# motor_driver.net
KiCad netlist of a schematic drawn in Altium Designer
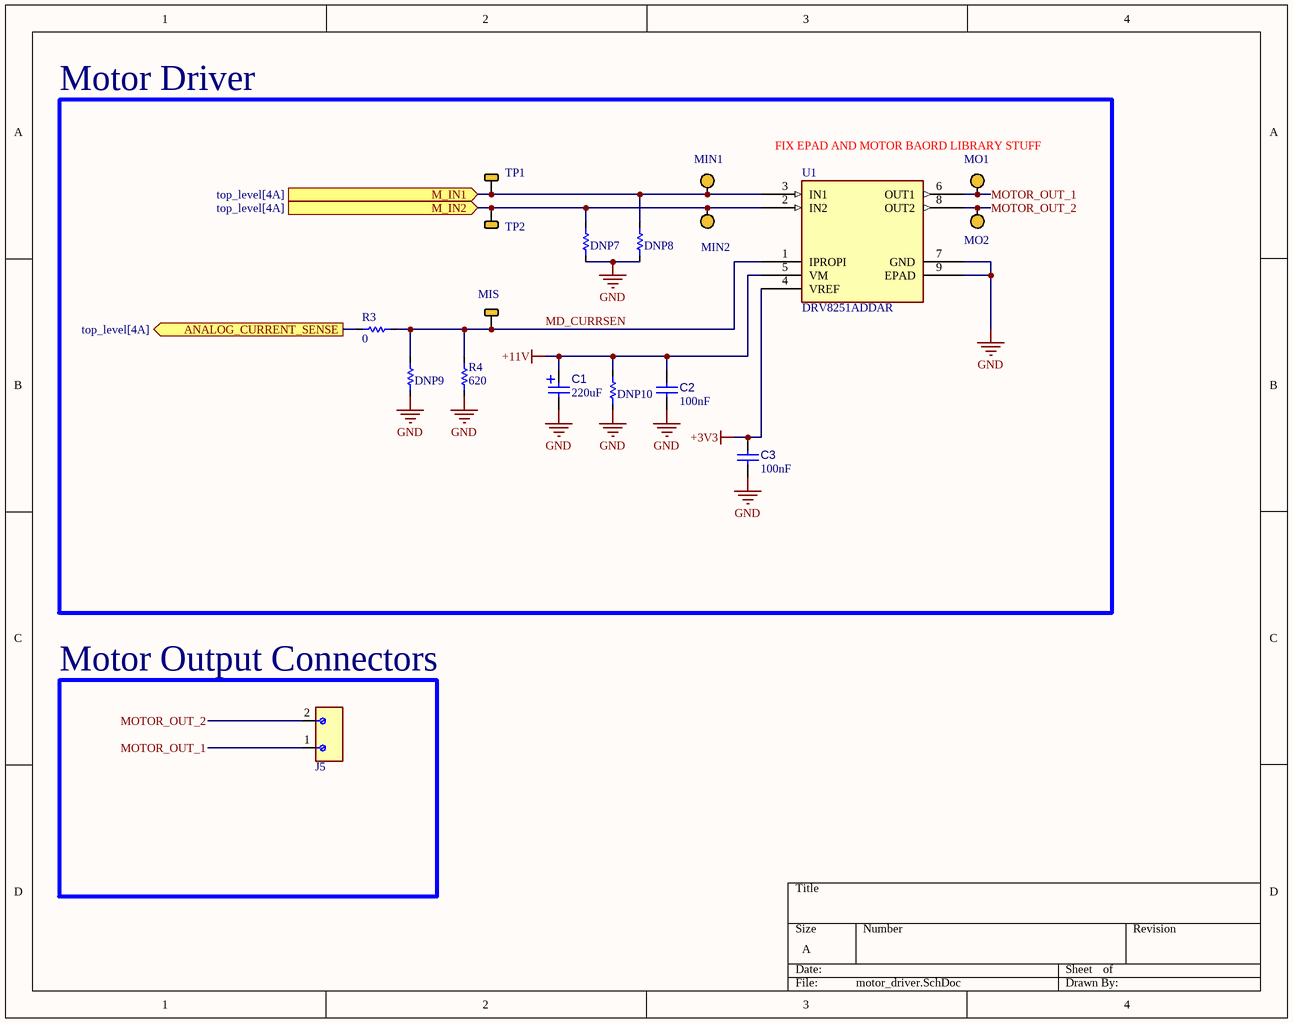
[diagram p0: motor_driver.SchDoc]

(export (version "E")
  (design (tool "Eeschema 10.0.6"))
  (components
    (comp (ref "C1")
      (value "220uF")
      (footprint "C - 860020574012")
      (description "860020574012 - 220 µF 35 V Aluminum Electrolytic Capacitors Radial, Can 2000 Hrs @ 105°C")
      (fields (field (name "Comment") "860020574012"))
      (libsource (lib "power_board_schhlib") (part "C - CAP ELC 220uF 35V 20% CAN"))
    )
    (comp (ref "C2")
      (value "100nF")
      (footprint "CAP_0603")
      (description "GRM188R72A104KA35D - 0.1 µF ±10% 100V Ceramic Capacitor X7R 0603 (1608 Metric)")
      (fields (field (name "Comment") "C - CAP CER 100nF 100V 10% 0603"))
      (libsource (lib "power_board_schhlib") (part "C - CAP CER 100nF 100V 10% 0603"))
    )
    (comp (ref "C3")
      (value "100nF")
      (footprint "CAP_0603")
      (description "GRM188R72A104KA35D - 0.1 µF ±10% 100V Ceramic Capacitor X7R 0603 (1608 Metric)")
      (fields (field (name "Comment") "C - CAP CER 100nF 100V 10% 0603"))
      (libsource (lib "power_board_schhlib") (part "C - CAP CER 100nF 100V 10% 0603"))
    )
    (comp (ref "DNP7")
      (value "DNP - DNP PAD 0603")
      (footprint "DNP 0603")
      (libsource (lib "motor_board_schhlib") (part "DNP - DNP PAD 0603"))
    )
    (comp (ref "DNP8")
      (value "DNP - DNP PAD 0603")
      (footprint "DNP 0603")
      (libsource (lib "motor_board_schhlib") (part "DNP - DNP PAD 0603"))
    )
    (comp (ref "DNP9")
      (value "DNP - DNP PAD 0603")
      (footprint "DNP 0603")
      (libsource (lib "motor_board_schhlib") (part "DNP - DNP PAD 0603"))
    )
    (comp (ref "DNP10")
      (value "DNP - DNP PAD 0603")
      (footprint "DNP 0603")
      (libsource (lib "motor_board_schhlib") (part "DNP - DNP PAD 0603"))
    )
    (comp (ref "J5")
      (value "J - 691137710002")
      (footprint "J - 691137710002")
      (libsource (lib "power_board_schhlib") (part "J - 691137710002"))
    )
    (comp (ref "MIN1")
      (value "TP - SMD Pad Test Point Circular")
      (footprint "TP - SMD Pad Testpoint")
      (description "Pad Test Point, Circular, 1mm Diameter.")
      (libsource (lib "motor_board_schhlib") (part "TP - SMD Pad Test Point Circular"))
    )
    (comp (ref "MIN2")
      (value "TP - SMD Pad Test Point Circular")
      (footprint "TP - SMD Pad Testpoint")
      (description "Pad Test Point, Circular, 1mm Diameter.")
      (libsource (lib "motor_board_schhlib") (part "TP - SMD Pad Test Point Circular"))
    )
    (comp (ref "MIS")
      (value "SMD Pad Testpoint Rectangular (Signal)")
      (footprint "SMD Pad Testpoint Rectangular (Signal)")
      (description "SMD Pad Test Point, No Stencil, Rectangular, 1mm Long, 0.3 (12mil) Wide, For Signal Traces.")
      (libsource (lib "motor_board_schhlib") (part "SMD Pad Testpoint Rectangular (Signal)"))
    )
    (comp (ref "MO1")
      (value "TP - SMD Pad Test Point Circular")
      (footprint "TP - SMD Pad Testpoint")
      (description "Pad Test Point, Circular, 1mm Diameter.")
      (libsource (lib "motor_board_schhlib") (part "TP - SMD Pad Test Point Circular"))
    )
    (comp (ref "MO2")
      (value "TP - SMD Pad Test Point Circular")
      (footprint "TP - SMD Pad Testpoint")
      (description "Pad Test Point, Circular, 1mm Diameter.")
      (libsource (lib "motor_board_schhlib") (part "TP - SMD Pad Test Point Circular"))
    )
    (comp (ref "R3")
      (value "0")
      (footprint "RES 0603")
      (description "ERJ-3GEY0R00V - 0 Ohms Jumper Chip Resistor 0603 (1608 Metric) Automotive AEC-Q200 Thick Film")
      (fields (field (name "Comment") "R - RES 0R 0.1W N/A% 0603"))
      (libsource (lib "motor_board_schhlib") (part "R - RES 0R 0.1W N/A% 0603"))
    )
    (comp (ref "R4")
      (value "620")
      (footprint "RES 0603")
      (fields (field (name "Comment") "R - RES 620R 0.33W 1% 0603"))
      (libsource (lib "motor_board_schhlib") (part "R - RES 620R 0.33W 1% 0603"))
    )
    (comp (ref "TP1")
      (value "SMD Pad Testpoint Rectangular (Signal)")
      (footprint "SMD Pad Testpoint Rectangular (Signal)")
      (description "SMD Pad Test Point, No Stencil, Rectangular, 1mm Long, 0.3 (12mil) Wide, For Signal Traces.")
      (libsource (lib "motor_board_schhlib") (part "SMD Pad Testpoint Rectangular (Signal)"))
    )
    (comp (ref "TP2")
      (value "SMD Pad Testpoint Rectangular (Signal)")
      (footprint "SMD Pad Testpoint Rectangular (Signal)")
      (description "SMD Pad Test Point, No Stencil, Rectangular, 1mm Long, 0.3 (12mil) Wide, For Signal Traces.")
      (libsource (lib "motor_board_schhlib") (part "SMD Pad Testpoint Rectangular (Signal)"))
    )
    (comp (ref "U1")
      (value "DRV8251ADDAR")
      (footprint "U - DRV8251ADDAR")
      (libsource (lib "motor_board_schhlib") (part "U - DRV8251ADDAR"))
    )
  )
  (nets
    (net (code "1") (name "+3V3") (class "Default")
      (node (ref "C3") (pin "2") (pinfunction "2_2") (pintype "passive"))
      (node (ref "U1") (pin "4") (pinfunction "VREF_4") (pintype "power_in"))
    )
    (net (code "2") (name "+11V") (class "Default")
      (node (ref "C1") (pin "1") (pinfunction "POS_1") (pintype "passive"))
      (node (ref "C2") (pin "2") (pinfunction "2_2") (pintype "passive"))
      (node (ref "DNP10") (pin "2") (pinfunction "2_2") (pintype "passive"))
      (node (ref "U1") (pin "5") (pinfunction "VM_5") (pintype "power_in"))
    )
    (net (code "3") (name "/ANALOG_CURRENT_SENSE") (class "Default")
      (node (ref "R3") (pin "1") (pinfunction "1_1") (pintype "passive"))
    )
    (net (code "4") (name "/MD_CURRSEN") (class "Default")
      (node (ref "DNP9") (pin "2") (pinfunction "2_2") (pintype "passive"))
      (node (ref "MIS") (pin "1") (pinfunction "1_1") (pintype "passive"))
      (node (ref "R3") (pin "2") (pinfunction "2_2") (pintype "passive"))
      (node (ref "R4") (pin "2") (pinfunction "2_2") (pintype "passive"))
      (node (ref "U1") (pin "1") (pinfunction "IPROPI_1") (pintype "power_in"))
    )
    (net (code "5") (name "/MOTOR_OUT_1") (class "Default")
      (node (ref "J5") (pin "1") (pinfunction "1_1") (pintype "passive"))
      (node (ref "MO1") (pin "1") (pinfunction "1_1") (pintype "passive"))
      (node (ref "U1") (pin "6") (pinfunction "OUT1_6") (pintype "output"))
    )
    (net (code "6") (name "/MOTOR_OUT_2") (class "Default")
      (node (ref "J5") (pin "2") (pinfunction "2_2") (pintype "passive"))
      (node (ref "MO2") (pin "1") (pinfunction "1_1") (pintype "passive"))
      (node (ref "U1") (pin "8") (pinfunction "OUT2_8") (pintype "output"))
    )
    (net (code "7") (name "/M_IN1") (class "Default")
      (node (ref "DNP8") (pin "2") (pinfunction "2_2") (pintype "passive"))
      (node (ref "MIN1") (pin "1") (pinfunction "1_1") (pintype "passive"))
      (node (ref "TP1") (pin "1") (pinfunction "1_1") (pintype "passive"))
      (node (ref "U1") (pin "3") (pinfunction "IN1_3") (pintype "input"))
    )
    (net (code "8") (name "/M_IN2") (class "Default")
      (node (ref "DNP7") (pin "2") (pinfunction "2_2") (pintype "passive"))
      (node (ref "MIN2") (pin "1") (pinfunction "1_1") (pintype "passive"))
      (node (ref "TP2") (pin "1") (pinfunction "1_1") (pintype "passive"))
      (node (ref "U1") (pin "2") (pinfunction "IN2_2") (pintype "input"))
    )
    (net (code "9") (name "GND") (class "Default")
      (node (ref "C1") (pin "2") (pinfunction "NEG_2") (pintype "passive"))
      (node (ref "C2") (pin "1") (pinfunction "1_1") (pintype "passive"))
      (node (ref "C3") (pin "1") (pinfunction "1_1") (pintype "passive"))
      (node (ref "DNP10") (pin "1") (pinfunction "1_1") (pintype "passive"))
      (node (ref "DNP7") (pin "1") (pinfunction "1_1") (pintype "passive"))
      (node (ref "DNP8") (pin "1") (pinfunction "1_1") (pintype "passive"))
      (node (ref "DNP9") (pin "1") (pinfunction "1_1") (pintype "passive"))
      (node (ref "R4") (pin "1") (pinfunction "1_1") (pintype "passive"))
      (node (ref "U1") (pin "7") (pinfunction "GND_7") (pintype "power_in"))
      (node (ref "U1") (pin "9") (pinfunction "EPAD_9") (pintype "power_in"))
    )
  )
)
